# Schematic.net
KiCad netlist of a schematic drawn in Altium Designer
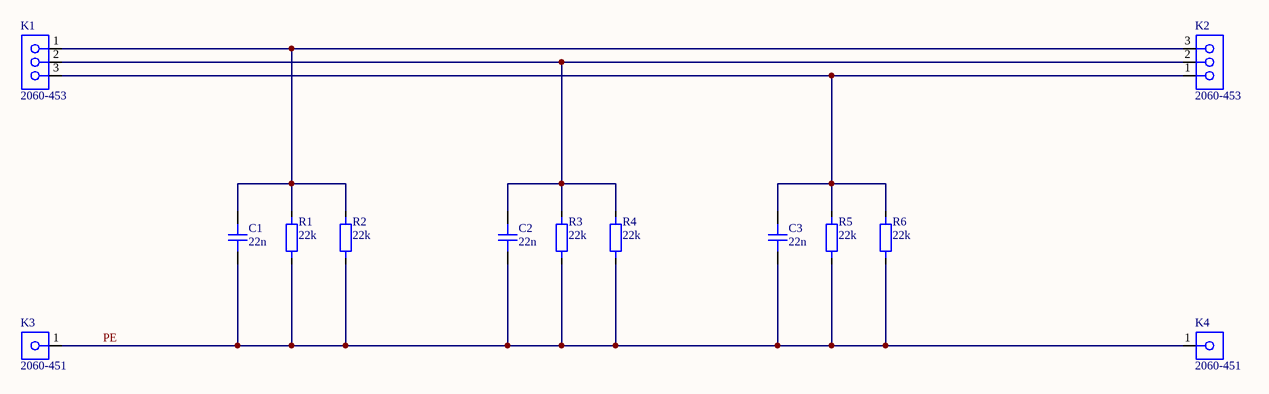
[diagram p0: Schematic.SchDoc]

(export (version "E")
  (design (tool "Eeschema 10.0.6"))
  (components
    (comp (ref "C1")
      (value "22n")
      (footprint "C-FOIL-18x13x7")
      (description "22n THT 10% Y2 MKP 300VAC")
      (fields (field (name "PART NUMBER") "C_22n_18x13x7_10%_300V_MKP"))
      (libsource (lib "Database_Libs") (part "C"))
    )
    (comp (ref "C2")
      (value "22n")
      (footprint "C-FOIL-18x13x7")
      (description "22n THT 10% Y2 MKP 300VAC")
      (fields (field (name "PART NUMBER") "C_22n_18x13x7_10%_300V_MKP"))
      (libsource (lib "Database_Libs") (part "C"))
    )
    (comp (ref "C3")
      (value "22n")
      (footprint "C-FOIL-18x13x7")
      (description "22n THT 10% Y2 MKP 300VAC")
      (fields (field (name "PART NUMBER") "C_22n_18x13x7_10%_300V_MKP"))
      (libsource (lib "Database_Libs") (part "C"))
    )
    (comp (ref "K1")
      (value "2060-453")
      (footprint "2060-453")
      (description "2060-453 3P Wago Spring Clamp Terminal SMD")
      (fields (field (name "PART NUMBER") "2060-453/998-404") (field (name "JLCPCB PART") "C2765056"))
      (libsource (lib "Database_Libs") (part "K-1x03"))
    )
    (comp (ref "K2")
      (value "2060-453")
      (footprint "2060-453")
      (description "2060-453 3P Wago Spring Clamp Terminal SMD")
      (fields (field (name "PART NUMBER") "2060-453/998-404") (field (name "JLCPCB PART") "C2765056"))
      (libsource (lib "Database_Libs") (part "K-1x03"))
    )
    (comp (ref "K3")
      (value "2060-451")
      (footprint "2060-451")
      (description "2060-451 1P Wago Spring Clamp Terminal SMD")
      (fields (field (name "PART NUMBER") "2060-451/998-404") (field (name "JLCPCB PART") "C2765054"))
      (libsource (lib "Database_Libs") (part "K-1x01"))
    )
    (comp (ref "K4")
      (value "2060-451")
      (footprint "2060-451")
      (description "2060-451 1P Wago Spring Clamp Terminal SMD")
      (fields (field (name "PART NUMBER") "2060-451/998-404") (field (name "JLCPCB PART") "C2765054"))
      (libsource (lib "Database_Libs") (part "K-1x01"))
    )
    (comp (ref "R1")
      (value "22k")
      (footprint "R1206")
      (description "22k SMD 1206 1% 200V 250mW")
      (fields (field (name "PART NUMBER") "R_22k_1206_1%_200V_250mW"))
      (libsource (lib "Database_Libs") (part "R"))
    )
    (comp (ref "R2")
      (value "22k")
      (footprint "R1206")
      (description "22k SMD 1206 1% 200V 250mW")
      (fields (field (name "PART NUMBER") "R_22k_1206_1%_200V_250mW"))
      (libsource (lib "Database_Libs") (part "R"))
    )
    (comp (ref "R3")
      (value "22k")
      (footprint "R1206")
      (description "22k SMD 1206 1% 200V 250mW")
      (fields (field (name "PART NUMBER") "R_22k_1206_1%_200V_250mW"))
      (libsource (lib "Database_Libs") (part "R"))
    )
    (comp (ref "R4")
      (value "22k")
      (footprint "R1206")
      (description "22k SMD 1206 1% 200V 250mW")
      (fields (field (name "PART NUMBER") "R_22k_1206_1%_200V_250mW"))
      (libsource (lib "Database_Libs") (part "R"))
    )
    (comp (ref "R5")
      (value "22k")
      (footprint "R1206")
      (description "22k SMD 1206 1% 200V 250mW")
      (fields (field (name "PART NUMBER") "R_22k_1206_1%_200V_250mW"))
      (libsource (lib "Database_Libs") (part "R"))
    )
    (comp (ref "R6")
      (value "22k")
      (footprint "R1206")
      (description "22k SMD 1206 1% 200V 250mW")
      (fields (field (name "PART NUMBER") "R_22k_1206_1%_200V_250mW"))
      (libsource (lib "Database_Libs") (part "R"))
    )
  )
  (nets
    (net (code "1") (name "/PE") (class "Default")
      (node (ref "C1") (pin "2") (pinfunction "2_2") (pintype "passive"))
      (node (ref "C2") (pin "2") (pinfunction "2_2") (pintype "passive"))
      (node (ref "C3") (pin "2") (pinfunction "2_2") (pintype "passive"))
      (node (ref "K3") (pin "1") (pintype "passive"))
      (node (ref "K4") (pin "1") (pintype "passive"))
      (node (ref "R1") (pin "1") (pinfunction "1_1") (pintype "passive"))
      (node (ref "R2") (pin "1") (pinfunction "1_1") (pintype "passive"))
      (node (ref "R3") (pin "1") (pinfunction "1_1") (pintype "passive"))
      (node (ref "R4") (pin "1") (pinfunction "1_1") (pintype "passive"))
      (node (ref "R5") (pin "1") (pinfunction "1_1") (pintype "passive"))
      (node (ref "R6") (pin "1") (pinfunction "1_1") (pintype "passive"))
    )
    (net (code "2") (name "Net-(C1-Pad1)") (class "Default")
      (node (ref "C1") (pin "1") (pinfunction "1_1") (pintype "passive"))
      (node (ref "K1") (pin "1") (pintype "passive"))
      (node (ref "K2") (pin "3") (pinfunction "3_3") (pintype "passive"))
      (node (ref "R1") (pin "2") (pinfunction "2_2") (pintype "passive"))
      (node (ref "R2") (pin "2") (pinfunction "2_2") (pintype "passive"))
    )
    (net (code "3") (name "Net-(C2-Pad1)") (class "Default")
      (node (ref "C2") (pin "1") (pinfunction "1_1") (pintype "passive"))
      (node (ref "K1") (pin "2") (pintype "passive"))
      (node (ref "K2") (pin "2") (pintype "passive"))
      (node (ref "R3") (pin "2") (pinfunction "2_2") (pintype "passive"))
      (node (ref "R4") (pin "2") (pinfunction "2_2") (pintype "passive"))
    )
    (net (code "4") (name "Net-(C3-Pad1)") (class "Default")
      (node (ref "C3") (pin "1") (pinfunction "1_1") (pintype "passive"))
      (node (ref "K1") (pin "3") (pinfunction "3_3") (pintype "passive"))
      (node (ref "K2") (pin "1") (pintype "passive"))
      (node (ref "R5") (pin "2") (pinfunction "2_2") (pintype "passive"))
      (node (ref "R6") (pin "2") (pinfunction "2_2") (pintype "passive"))
    )
  )
)
